# display.net
KiCad netlist of a schematic drawn in EAGLE
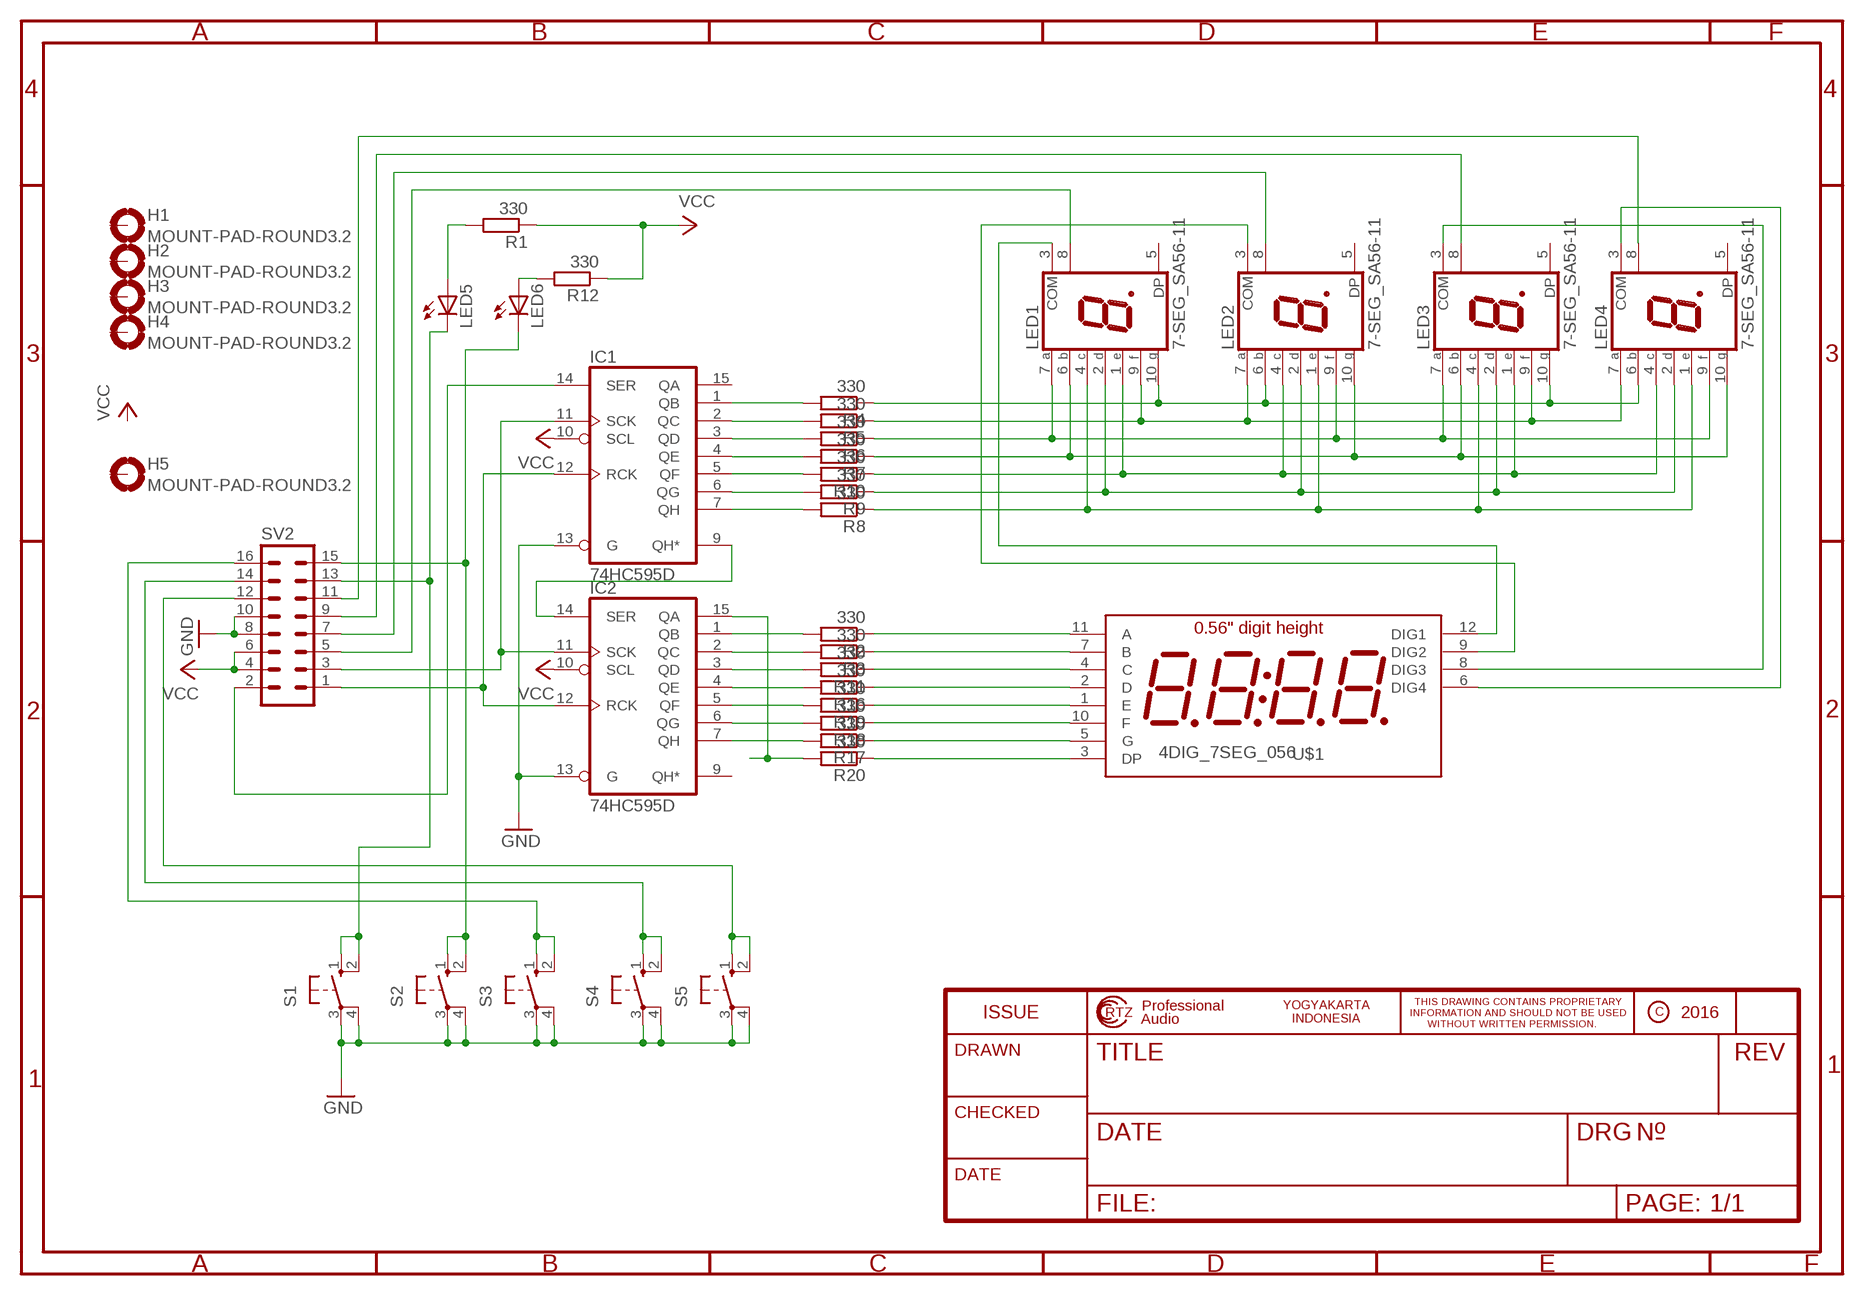
[diagram p0: schematic, sheet 1]

(export (version "E")
  (design (tool "Eeschema 10.0.6"))
  (components
    (comp (ref "H1")
      (value "MOUNT-PAD-ROUND3.2")
      (footprint "eagle-import:3,2-PAD")
      (libsource (lib "eagle-import") (part "MOUNT-PAD-ROUND3.2"))
    )
    (comp (ref "H2")
      (value "MOUNT-PAD-ROUND3.2")
      (footprint "eagle-import:3,2-PAD")
      (libsource (lib "eagle-import") (part "MOUNT-PAD-ROUND3.2"))
    )
    (comp (ref "H3")
      (value "MOUNT-PAD-ROUND3.2")
      (footprint "eagle-import:3,2-PAD")
      (libsource (lib "eagle-import") (part "MOUNT-PAD-ROUND3.2"))
    )
    (comp (ref "H4")
      (value "MOUNT-PAD-ROUND3.2")
      (footprint "eagle-import:3,2-PAD")
      (libsource (lib "eagle-import") (part "MOUNT-PAD-ROUND3.2"))
    )
    (comp (ref "H5")
      (value "MOUNT-PAD-ROUND3.2")
      (footprint "eagle-import:3,2-PAD")
      (libsource (lib "eagle-import") (part "MOUNT-PAD-ROUND3.2"))
    )
    (comp (ref "IC1")
      (value "74HC595D")
      (footprint "eagle-import:SO16")
      (libsource (lib "eagle-import") (part "74595DHC"))
    )
    (comp (ref "IC2")
      (value "74HC595D")
      (footprint "eagle-import:SO16")
      (libsource (lib "eagle-import") (part "74595DHC"))
    )
    (comp (ref "LED1")
      (value "7-SEG_SA56-11")
      (footprint "eagle-import:SA56-11")
      (libsource (lib "eagle-import") (part "7-SEG_SA56-11"))
    )
    (comp (ref "LED2")
      (value "7-SEG_SA56-11")
      (footprint "eagle-import:SA56-11")
      (libsource (lib "eagle-import") (part "7-SEG_SA56-11"))
    )
    (comp (ref "LED3")
      (value "7-SEG_SA56-11")
      (footprint "eagle-import:SA56-11")
      (libsource (lib "eagle-import") (part "7-SEG_SA56-11"))
    )
    (comp (ref "LED4")
      (value "7-SEG_SA56-11")
      (footprint "eagle-import:SA56-11")
      (libsource (lib "eagle-import") (part "7-SEG_SA56-11"))
    )
    (comp (ref "LED5")
      (value "LED5MM")
      (footprint "eagle-import:LED5MM")
      (libsource (lib "eagle-import") (part "LED5MM"))
    )
    (comp (ref "LED6")
      (value "LED5MM")
      (footprint "eagle-import:LED5MM")
      (libsource (lib "eagle-import") (part "LED5MM"))
    )
    (comp (ref "R1")
      (value "330")
      (footprint "eagle-import:0207_7")
      (libsource (lib "eagle-import") (part "R-EU_0207/7"))
    )
    (comp (ref "R2")
      (value "330")
      (footprint "eagle-import:0207_7")
      (libsource (lib "eagle-import") (part "R-EU_0207/7"))
    )
    (comp (ref "R3")
      (value "330")
      (footprint "eagle-import:0207_7")
      (libsource (lib "eagle-import") (part "R-EU_0207/7"))
    )
    (comp (ref "R4")
      (value "330")
      (footprint "eagle-import:0207_7")
      (libsource (lib "eagle-import") (part "R-EU_0207/7"))
    )
    (comp (ref "R5")
      (value "330")
      (footprint "eagle-import:0207_7")
      (libsource (lib "eagle-import") (part "R-EU_0207/7"))
    )
    (comp (ref "R6")
      (value "330")
      (footprint "eagle-import:0207_7")
      (libsource (lib "eagle-import") (part "R-EU_0207/7"))
    )
    (comp (ref "R7")
      (value "330")
      (footprint "eagle-import:0207_7")
      (libsource (lib "eagle-import") (part "R-EU_0207/7"))
    )
    (comp (ref "R8")
      (value "330")
      (footprint "eagle-import:0207_7")
      (libsource (lib "eagle-import") (part "R-EU_0207/7"))
    )
    (comp (ref "R9")
      (value "330")
      (footprint "eagle-import:0207_7")
      (libsource (lib "eagle-import") (part "R-EU_0207/7"))
    )
    (comp (ref "R10")
      (value "330")
      (footprint "eagle-import:0207_7")
      (libsource (lib "eagle-import") (part "R-EU_0207/7"))
    )
    (comp (ref "R11")
      (value "330")
      (footprint "eagle-import:0207_7")
      (libsource (lib "eagle-import") (part "R-EU_0207/7"))
    )
    (comp (ref "R12")
      (value "330")
      (footprint "eagle-import:0207_7")
      (libsource (lib "eagle-import") (part "R-EU_0207/7"))
    )
    (comp (ref "R16")
      (value "330")
      (footprint "eagle-import:0207_7")
      (libsource (lib "eagle-import") (part "R-EU_0207/7"))
    )
    (comp (ref "R17")
      (value "330")
      (footprint "eagle-import:0207_7")
      (libsource (lib "eagle-import") (part "R-EU_0207/7"))
    )
    (comp (ref "R18")
      (value "330")
      (footprint "eagle-import:0207_7")
      (libsource (lib "eagle-import") (part "R-EU_0207/7"))
    )
    (comp (ref "R19")
      (value "330")
      (footprint "eagle-import:0207_7")
      (libsource (lib "eagle-import") (part "R-EU_0207/7"))
    )
    (comp (ref "R20")
      (value "330")
      (footprint "eagle-import:0207_7")
      (libsource (lib "eagle-import") (part "R-EU_0207/7"))
    )
    (comp (ref "S1")
      (value "40-XX")
      (footprint "eagle-import:B3F-40XX")
      (fields (field (name "MF") "OMRON COMPONENTS USA") (field (name "MPN") "B3F-4000"))
      (libsource (lib "eagle-import") (part "40-XX"))
    )
    (comp (ref "S2")
      (value "40-XX")
      (footprint "eagle-import:B3F-40XX")
      (fields (field (name "MF") "OMRON COMPONENTS USA") (field (name "MPN") "B3F-4000"))
      (libsource (lib "eagle-import") (part "40-XX"))
    )
    (comp (ref "S3")
      (value "40-XX")
      (footprint "eagle-import:B3F-40XX")
      (fields (field (name "MF") "OMRON COMPONENTS USA") (field (name "MPN") "B3F-4000"))
      (libsource (lib "eagle-import") (part "40-XX"))
    )
    (comp (ref "S4")
      (value "40-XX")
      (footprint "eagle-import:B3F-40XX")
      (fields (field (name "MF") "OMRON COMPONENTS USA") (field (name "MPN") "B3F-4000"))
      (libsource (lib "eagle-import") (part "40-XX"))
    )
    (comp (ref "S5")
      (value "40-XX")
      (footprint "eagle-import:B3F-40XX")
      (fields (field (name "MF") "OMRON COMPONENTS USA") (field (name "MPN") "B3F-4000"))
      (libsource (lib "eagle-import") (part "40-XX"))
    )
    (comp (ref "SV2")
      (value "MA08-2W")
      (footprint "eagle-import:MA08-2W")
      (libsource (lib "eagle-import") (part "MA08-2W"))
    )
    (comp (ref "U$1")
      (value "4DIG_7SEG_056")
      (footprint "eagle-import:4DIG_7SEG_056")
      (libsource (lib "eagle-import") (part "4DIG_7SEG_056"))
    )
  )
  (nets
    (net (code "1") (name "GND") (class "Default")
      (node (ref "IC1") (pin "13") (pinfunction "G_13") (pintype "input"))
      (node (ref "IC2") (pin "13") (pinfunction "G_13") (pintype "input"))
      (node (ref "S1") (pin "3") (pinfunction "P_3") (pintype "passive"))
      (node (ref "S1") (pin "4") (pinfunction "P1_4") (pintype "passive"))
      (node (ref "S2") (pin "3") (pinfunction "P_3") (pintype "passive"))
      (node (ref "S2") (pin "4") (pinfunction "P1_4") (pintype "passive"))
      (node (ref "S3") (pin "3") (pinfunction "P_3") (pintype "passive"))
      (node (ref "S3") (pin "4") (pinfunction "P1_4") (pintype "passive"))
      (node (ref "S4") (pin "3") (pinfunction "P_3") (pintype "passive"))
      (node (ref "S4") (pin "4") (pinfunction "P1_4") (pintype "passive"))
      (node (ref "S5") (pin "3") (pinfunction "P_3") (pintype "passive"))
      (node (ref "S5") (pin "4") (pinfunction "P1_4") (pintype "passive"))
      (node (ref "SV2") (pin "10") (pinfunction "10_10") (pintype "passive"))
      (node (ref "SV2") (pin "8") (pinfunction "8_8") (pintype "passive"))
    )
    (net (code "2") (name "Net-(IC1A-QB)") (class "Default")
      (node (ref "IC1") (pin "1") (pinfunction "QB_1") (pintype "tri_state"))
      (node (ref "R4") (pin "2") (pinfunction "2_2") (pintype "passive"))
    )
    (net (code "3") (name "Net-(IC1A-QC)") (class "Default")
      (node (ref "IC1") (pin "2") (pinfunction "QC_2") (pintype "tri_state"))
      (node (ref "R5") (pin "2") (pinfunction "2_2") (pintype "passive"))
    )
    (net (code "4") (name "Net-(IC1A-QD)") (class "Default")
      (node (ref "IC1") (pin "3") (pinfunction "QD_3") (pintype "tri_state"))
      (node (ref "R6") (pin "2") (pinfunction "2_2") (pintype "passive"))
    )
    (net (code "5") (name "Net-(IC1A-QE)") (class "Default")
      (node (ref "IC1") (pin "4") (pinfunction "QE_4") (pintype "tri_state"))
      (node (ref "R7") (pin "2") (pinfunction "2_2") (pintype "passive"))
    )
    (net (code "6") (name "Net-(IC1A-QF)") (class "Default")
      (node (ref "IC1") (pin "5") (pinfunction "QF_5") (pintype "tri_state"))
      (node (ref "R10") (pin "2") (pinfunction "2_2") (pintype "passive"))
    )
    (net (code "7") (name "Net-(IC1A-QG)") (class "Default")
      (node (ref "IC1") (pin "6") (pinfunction "QG_6") (pintype "tri_state"))
      (node (ref "R9") (pin "2") (pinfunction "2_2") (pintype "passive"))
    )
    (net (code "8") (name "Net-(IC1A-QH)") (class "Default")
      (node (ref "IC1") (pin "7") (pinfunction "QH_7") (pintype "tri_state"))
      (node (ref "R8") (pin "2") (pinfunction "2_2") (pintype "passive"))
    )
    (net (code "9") (name "Net-(IC1A-QH*)") (class "Default")
      (node (ref "IC1") (pin "9") (pinfunction "QH*_9") (pintype "tri_state"))
      (node (ref "IC2") (pin "14") (pinfunction "SER_14") (pintype "input"))
    )
    (net (code "10") (name "Net-(IC1A-RCK)") (class "Default")
      (node (ref "IC1") (pin "12") (pinfunction "RCK_12") (pintype "input"))
      (node (ref "IC2") (pin "12") (pinfunction "RCK_12") (pintype "input"))
      (node (ref "SV2") (pin "1") (pinfunction "1_1") (pintype "passive"))
    )
    (net (code "11") (name "Net-(IC1A-SCK)") (class "Default")
      (node (ref "IC1") (pin "11") (pinfunction "SCK_11") (pintype "input"))
      (node (ref "IC2") (pin "11") (pinfunction "SCK_11") (pintype "input"))
      (node (ref "SV2") (pin "3") (pinfunction "3_3") (pintype "passive"))
    )
    (net (code "12") (name "Net-(IC1A-SER)") (class "Default")
      (node (ref "IC1") (pin "14") (pinfunction "SER_14") (pintype "input"))
      (node (ref "SV2") (pin "2") (pinfunction "2_2") (pintype "passive"))
    )
    (net (code "13") (name "Net-(IC2A-QA)") (class "Default")
      (node (ref "IC2") (pin "15") (pinfunction "QA_15") (pintype "tri_state"))
      (node (ref "R20") (pin "2") (pinfunction "2_2") (pintype "passive"))
    )
    (net (code "14") (name "Net-(IC2A-QB)") (class "Default")
      (node (ref "IC2") (pin "1") (pinfunction "QB_1") (pintype "tri_state"))
      (node (ref "R2") (pin "2") (pinfunction "2_2") (pintype "passive"))
    )
    (net (code "15") (name "Net-(IC2A-QC)") (class "Default")
      (node (ref "IC2") (pin "2") (pinfunction "QC_2") (pintype "tri_state"))
      (node (ref "R3") (pin "2") (pinfunction "2_2") (pintype "passive"))
    )
    (net (code "16") (name "Net-(IC2A-QD)") (class "Default")
      (node (ref "IC2") (pin "3") (pinfunction "QD_3") (pintype "tri_state"))
      (node (ref "R11") (pin "2") (pinfunction "2_2") (pintype "passive"))
    )
    (net (code "17") (name "Net-(IC2A-QE)") (class "Default")
      (node (ref "IC2") (pin "4") (pinfunction "QE_4") (pintype "tri_state"))
      (node (ref "R16") (pin "2") (pinfunction "2_2") (pintype "passive"))
    )
    (net (code "18") (name "Net-(IC2A-QF)") (class "Default")
      (node (ref "IC2") (pin "5") (pinfunction "QF_5") (pintype "tri_state"))
      (node (ref "R19") (pin "2") (pinfunction "2_2") (pintype "passive"))
    )
    (net (code "19") (name "Net-(IC2A-QG)") (class "Default")
      (node (ref "IC2") (pin "6") (pinfunction "QG_6") (pintype "tri_state"))
      (node (ref "R18") (pin "2") (pinfunction "2_2") (pintype "passive"))
    )
    (net (code "20") (name "Net-(IC2A-QH)") (class "Default")
      (node (ref "IC2") (pin "7") (pinfunction "QH_7") (pintype "tri_state"))
      (node (ref "R17") (pin "2") (pinfunction "2_2") (pintype "passive"))
    )
    (net (code "21") (name "Net-(LED1-A)") (class "Default")
      (node (ref "LED1") (pin "7") (pinfunction "A_7") (pintype "passive"))
      (node (ref "LED2") (pin "9") (pinfunction "F_9") (pintype "passive"))
      (node (ref "LED3") (pin "7") (pinfunction "A_7") (pintype "passive"))
      (node (ref "LED4") (pin "9") (pinfunction "F_9") (pintype "passive"))
      (node (ref "R6") (pin "1") (pinfunction "1_1") (pintype "passive"))
    )
    (net (code "22") (name "Net-(LED1-B)") (class "Default")
      (node (ref "LED1") (pin "6") (pinfunction "B_6") (pintype "passive"))
      (node (ref "LED2") (pin "10") (pinfunction "G_10") (pintype "passive"))
      (node (ref "LED3") (pin "6") (pinfunction "B_6") (pintype "passive"))
      (node (ref "LED4") (pin "10") (pinfunction "G_10") (pintype "passive"))
      (node (ref "R7") (pin "1") (pinfunction "1_1") (pintype "passive"))
    )
    (net (code "23") (name "Net-(LED1-C)") (class "Default")
      (node (ref "LED1") (pin "4") (pinfunction "C_4") (pintype "passive"))
      (node (ref "LED2") (pin "1") (pinfunction "E_1") (pintype "passive"))
      (node (ref "LED3") (pin "4") (pinfunction "C_4") (pintype "passive"))
      (node (ref "LED4") (pin "1") (pinfunction "E_1") (pintype "passive"))
      (node (ref "R8") (pin "1") (pinfunction "1_1") (pintype "passive"))
    )
    (net (code "24") (name "Net-(LED1-COM-Pad8)") (class "Default")
      (node (ref "LED1") (pin "8") (pinfunction "COM_8") (pintype "passive"))
      (node (ref "SV2") (pin "5") (pinfunction "5_5") (pintype "passive"))
    )
    (net (code "25") (name "Net-(LED1-D)") (class "Default")
      (node (ref "LED1") (pin "2") (pinfunction "D_2") (pintype "passive"))
      (node (ref "LED2") (pin "2") (pinfunction "D_2") (pintype "passive"))
      (node (ref "LED3") (pin "2") (pinfunction "D_2") (pintype "passive"))
      (node (ref "LED4") (pin "2") (pinfunction "D_2") (pintype "passive"))
      (node (ref "R9") (pin "1") (pinfunction "1_1") (pintype "passive"))
    )
    (net (code "26") (name "Net-(LED1-E)") (class "Default")
      (node (ref "LED1") (pin "1") (pinfunction "E_1") (pintype "passive"))
      (node (ref "LED2") (pin "4") (pinfunction "C_4") (pintype "passive"))
      (node (ref "LED3") (pin "1") (pinfunction "E_1") (pintype "passive"))
      (node (ref "LED4") (pin "4") (pinfunction "C_4") (pintype "passive"))
      (node (ref "R10") (pin "1") (pinfunction "1_1") (pintype "passive"))
    )
    (net (code "27") (name "Net-(LED1-F)") (class "Default")
      (node (ref "LED1") (pin "9") (pinfunction "F_9") (pintype "passive"))
      (node (ref "LED2") (pin "7") (pinfunction "A_7") (pintype "passive"))
      (node (ref "LED3") (pin "9") (pinfunction "F_9") (pintype "passive"))
      (node (ref "LED4") (pin "7") (pinfunction "A_7") (pintype "passive"))
      (node (ref "R5") (pin "1") (pinfunction "1_1") (pintype "passive"))
    )
    (net (code "28") (name "Net-(LED1-G)") (class "Default")
      (node (ref "LED1") (pin "10") (pinfunction "G_10") (pintype "passive"))
      (node (ref "LED2") (pin "6") (pinfunction "B_6") (pintype "passive"))
      (node (ref "LED3") (pin "10") (pinfunction "G_10") (pintype "passive"))
      (node (ref "LED4") (pin "6") (pinfunction "B_6") (pintype "passive"))
      (node (ref "R4") (pin "1") (pinfunction "1_1") (pintype "passive"))
    )
    (net (code "29") (name "Net-(LED2-COM-Pad8)") (class "Default")
      (node (ref "LED2") (pin "8") (pinfunction "COM_8") (pintype "passive"))
      (node (ref "SV2") (pin "7") (pinfunction "7_7") (pintype "passive"))
    )
    (net (code "30") (name "Net-(LED3-COM-Pad8)") (class "Default")
      (node (ref "LED3") (pin "8") (pinfunction "COM_8") (pintype "passive"))
      (node (ref "SV2") (pin "9") (pinfunction "9_9") (pintype "passive"))
    )
    (net (code "31") (name "Net-(LED4-COM-Pad8)") (class "Default")
      (node (ref "LED4") (pin "8") (pinfunction "COM_8") (pintype "passive"))
      (node (ref "SV2") (pin "11") (pinfunction "11_11") (pintype "passive"))
    )
    (net (code "32") (name "Net-(LED5-C)") (class "Default")
      (node (ref "LED5") (pin "K") (pinfunction "C_K") (pintype "passive"))
      (node (ref "S1") (pin "1") (pinfunction "S_1") (pintype "passive"))
      (node (ref "S1") (pin "2") (pinfunction "S1_2") (pintype "passive"))
      (node (ref "SV2") (pin "13") (pinfunction "13_13") (pintype "passive"))
    )
    (net (code "33") (name "Net-(LED5-PadA)") (class "Default")
      (node (ref "LED5") (pin "A") (pinfunction "A_A") (pintype "passive"))
      (node (ref "R1") (pin "2") (pinfunction "2_2") (pintype "passive"))
    )
    (net (code "34") (name "Net-(LED6-C)") (class "Default")
      (node (ref "LED6") (pin "K") (pinfunction "C_K") (pintype "passive"))
      (node (ref "S2") (pin "1") (pinfunction "S_1") (pintype "passive"))
      (node (ref "S2") (pin "2") (pinfunction "S1_2") (pintype "passive"))
      (node (ref "SV2") (pin "15") (pinfunction "15_15") (pintype "passive"))
    )
    (net (code "35") (name "Net-(LED6-PadA)") (class "Default")
      (node (ref "LED6") (pin "A") (pinfunction "A_A") (pintype "passive"))
      (node (ref "R12") (pin "2") (pinfunction "2_2") (pintype "passive"))
    )
    (net (code "36") (name "Net-(S3-S)") (class "Default")
      (node (ref "S3") (pin "1") (pinfunction "S_1") (pintype "passive"))
      (node (ref "S3") (pin "2") (pinfunction "S1_2") (pintype "passive"))
      (node (ref "SV2") (pin "16") (pinfunction "16_16") (pintype "passive"))
    )
    (net (code "37") (name "Net-(S4-S)") (class "Default")
      (node (ref "S4") (pin "1") (pinfunction "S_1") (pintype "passive"))
      (node (ref "S4") (pin "2") (pinfunction "S1_2") (pintype "passive"))
      (node (ref "SV2") (pin "14") (pinfunction "14_14") (pintype "passive"))
    )
    (net (code "38") (name "Net-(S5-S)") (class "Default")
      (node (ref "S5") (pin "1") (pinfunction "S_1") (pintype "passive"))
      (node (ref "S5") (pin "2") (pinfunction "S1_2") (pintype "passive"))
      (node (ref "SV2") (pin "12") (pinfunction "12_12") (pintype "passive"))
    )
    (net (code "39") (name "Net-(U$1-A)") (class "Default")
      (node (ref "R2") (pin "1") (pinfunction "1_1") (pintype "passive"))
      (node (ref "U$1") (pin "11") (pinfunction "A_11") (pintype "bidirectional"))
    )
    (net (code "40") (name "Net-(U$1-B)") (class "Default")
      (node (ref "R3") (pin "1") (pinfunction "1_1") (pintype "passive"))
      (node (ref "U$1") (pin "7") (pinfunction "B_7") (pintype "bidirectional"))
    )
    (net (code "41") (name "Net-(U$1-C)") (class "Default")
      (node (ref "R11") (pin "1") (pinfunction "1_1") (pintype "passive"))
      (node (ref "U$1") (pin "4") (pinfunction "C_4") (pintype "bidirectional"))
    )
    (net (code "42") (name "Net-(U$1-D)") (class "Default")
      (node (ref "R16") (pin "1") (pinfunction "1_1") (pintype "passive"))
      (node (ref "U$1") (pin "2") (pinfunction "D_2") (pintype "bidirectional"))
    )
    (net (code "43") (name "Net-(U$1-DIG1)") (class "Default")
      (node (ref "LED1") (pin "3") (pinfunction "COM_3") (pintype "passive"))
      (node (ref "U$1") (pin "12") (pinfunction "DIG1_12") (pintype "bidirectional"))
    )
    (net (code "44") (name "Net-(U$1-DIG2)") (class "Default")
      (node (ref "LED2") (pin "3") (pinfunction "COM_3") (pintype "passive"))
      (node (ref "U$1") (pin "9") (pinfunction "DIG2_9") (pintype "bidirectional"))
    )
    (net (code "45") (name "Net-(U$1-DIG3)") (class "Default")
      (node (ref "LED3") (pin "3") (pinfunction "COM_3") (pintype "passive"))
      (node (ref "U$1") (pin "8") (pinfunction "DIG3_8") (pintype "bidirectional"))
    )
    (net (code "46") (name "Net-(U$1-DIG4)") (class "Default")
      (node (ref "LED4") (pin "3") (pinfunction "COM_3") (pintype "passive"))
      (node (ref "U$1") (pin "6") (pinfunction "DIG4_6") (pintype "bidirectional"))
    )
    (net (code "47") (name "Net-(U$1-DP)") (class "Default")
      (node (ref "R20") (pin "1") (pinfunction "1_1") (pintype "passive"))
      (node (ref "U$1") (pin "3") (pinfunction "DP_3") (pintype "bidirectional"))
    )
    (net (code "48") (name "Net-(U$1-E)") (class "Default")
      (node (ref "R19") (pin "1") (pinfunction "1_1") (pintype "passive"))
      (node (ref "U$1") (pin "1") (pinfunction "E_1") (pintype "bidirectional"))
    )
    (net (code "49") (name "Net-(U$1-F)") (class "Default")
      (node (ref "R18") (pin "1") (pinfunction "1_1") (pintype "passive"))
      (node (ref "U$1") (pin "10") (pinfunction "F_10") (pintype "bidirectional"))
    )
    (net (code "50") (name "Net-(U$1-G)") (class "Default")
      (node (ref "R17") (pin "1") (pinfunction "1_1") (pintype "passive"))
      (node (ref "U$1") (pin "5") (pinfunction "G_5") (pintype "bidirectional"))
    )
    (net (code "51") (name "VCC") (class "Default")
      (node (ref "IC1") (pin "10") (pinfunction "SCL_10") (pintype "input"))
      (node (ref "IC2") (pin "10") (pinfunction "SCL_10") (pintype "input"))
      (node (ref "R1") (pin "1") (pinfunction "1_1") (pintype "passive"))
      (node (ref "R12") (pin "1") (pinfunction "1_1") (pintype "passive"))
      (node (ref "SV2") (pin "4") (pinfunction "4_4") (pintype "passive"))
      (node (ref "SV2") (pin "6") (pinfunction "6_6") (pintype "passive"))
    )
    (net (code "52") (name "unconnected-(H1-MOUNT-PadB3,2)") (class "Default")
      (node (ref "H1") (pin "B3,2") (pinfunction "MOUNT_B3,2") (pintype "passive"))
    )
    (net (code "53") (name "unconnected-(H2-MOUNT-PadB3,2)") (class "Default")
      (node (ref "H2") (pin "B3,2") (pinfunction "MOUNT_B3,2") (pintype "passive"))
    )
    (net (code "54") (name "unconnected-(H3-MOUNT-PadB3,2)") (class "Default")
      (node (ref "H3") (pin "B3,2") (pinfunction "MOUNT_B3,2") (pintype "passive"))
    )
    (net (code "55") (name "unconnected-(H4-MOUNT-PadB3,2)") (class "Default")
      (node (ref "H4") (pin "B3,2") (pinfunction "MOUNT_B3,2") (pintype "passive"))
    )
    (net (code "56") (name "unconnected-(H5-MOUNT-PadB3,2)") (class "Default")
      (node (ref "H5") (pin "B3,2") (pinfunction "MOUNT_B3,2") (pintype "passive"))
    )
    (net (code "57") (name "unconnected-(IC1A-QA-Pad15)") (class "Default")
      (node (ref "IC1") (pin "15") (pinfunction "QA_15") (pintype "tri_state"))
    )
    (net (code "58") (name "unconnected-(IC2A-QH*-Pad9)") (class "Default")
      (node (ref "IC2") (pin "9") (pinfunction "QH*_9") (pintype "tri_state"))
    )
    (net (code "59") (name "unconnected-(LED1-DP-Pad5)") (class "Default")
      (node (ref "LED1") (pin "5") (pinfunction "DP_5") (pintype "passive"))
    )
    (net (code "60") (name "unconnected-(LED2-DP-Pad5)") (class "Default")
      (node (ref "LED2") (pin "5") (pinfunction "DP_5") (pintype "passive"))
    )
    (net (code "61") (name "unconnected-(LED3-DP-Pad5)") (class "Default")
      (node (ref "LED3") (pin "5") (pinfunction "DP_5") (pintype "passive"))
    )
    (net (code "62") (name "unconnected-(LED4-DP-Pad5)") (class "Default")
      (node (ref "LED4") (pin "5") (pinfunction "DP_5") (pintype "passive"))
    )
  )
)
